# shield.net
KiCad netlist of a schematic drawn in EAGLE
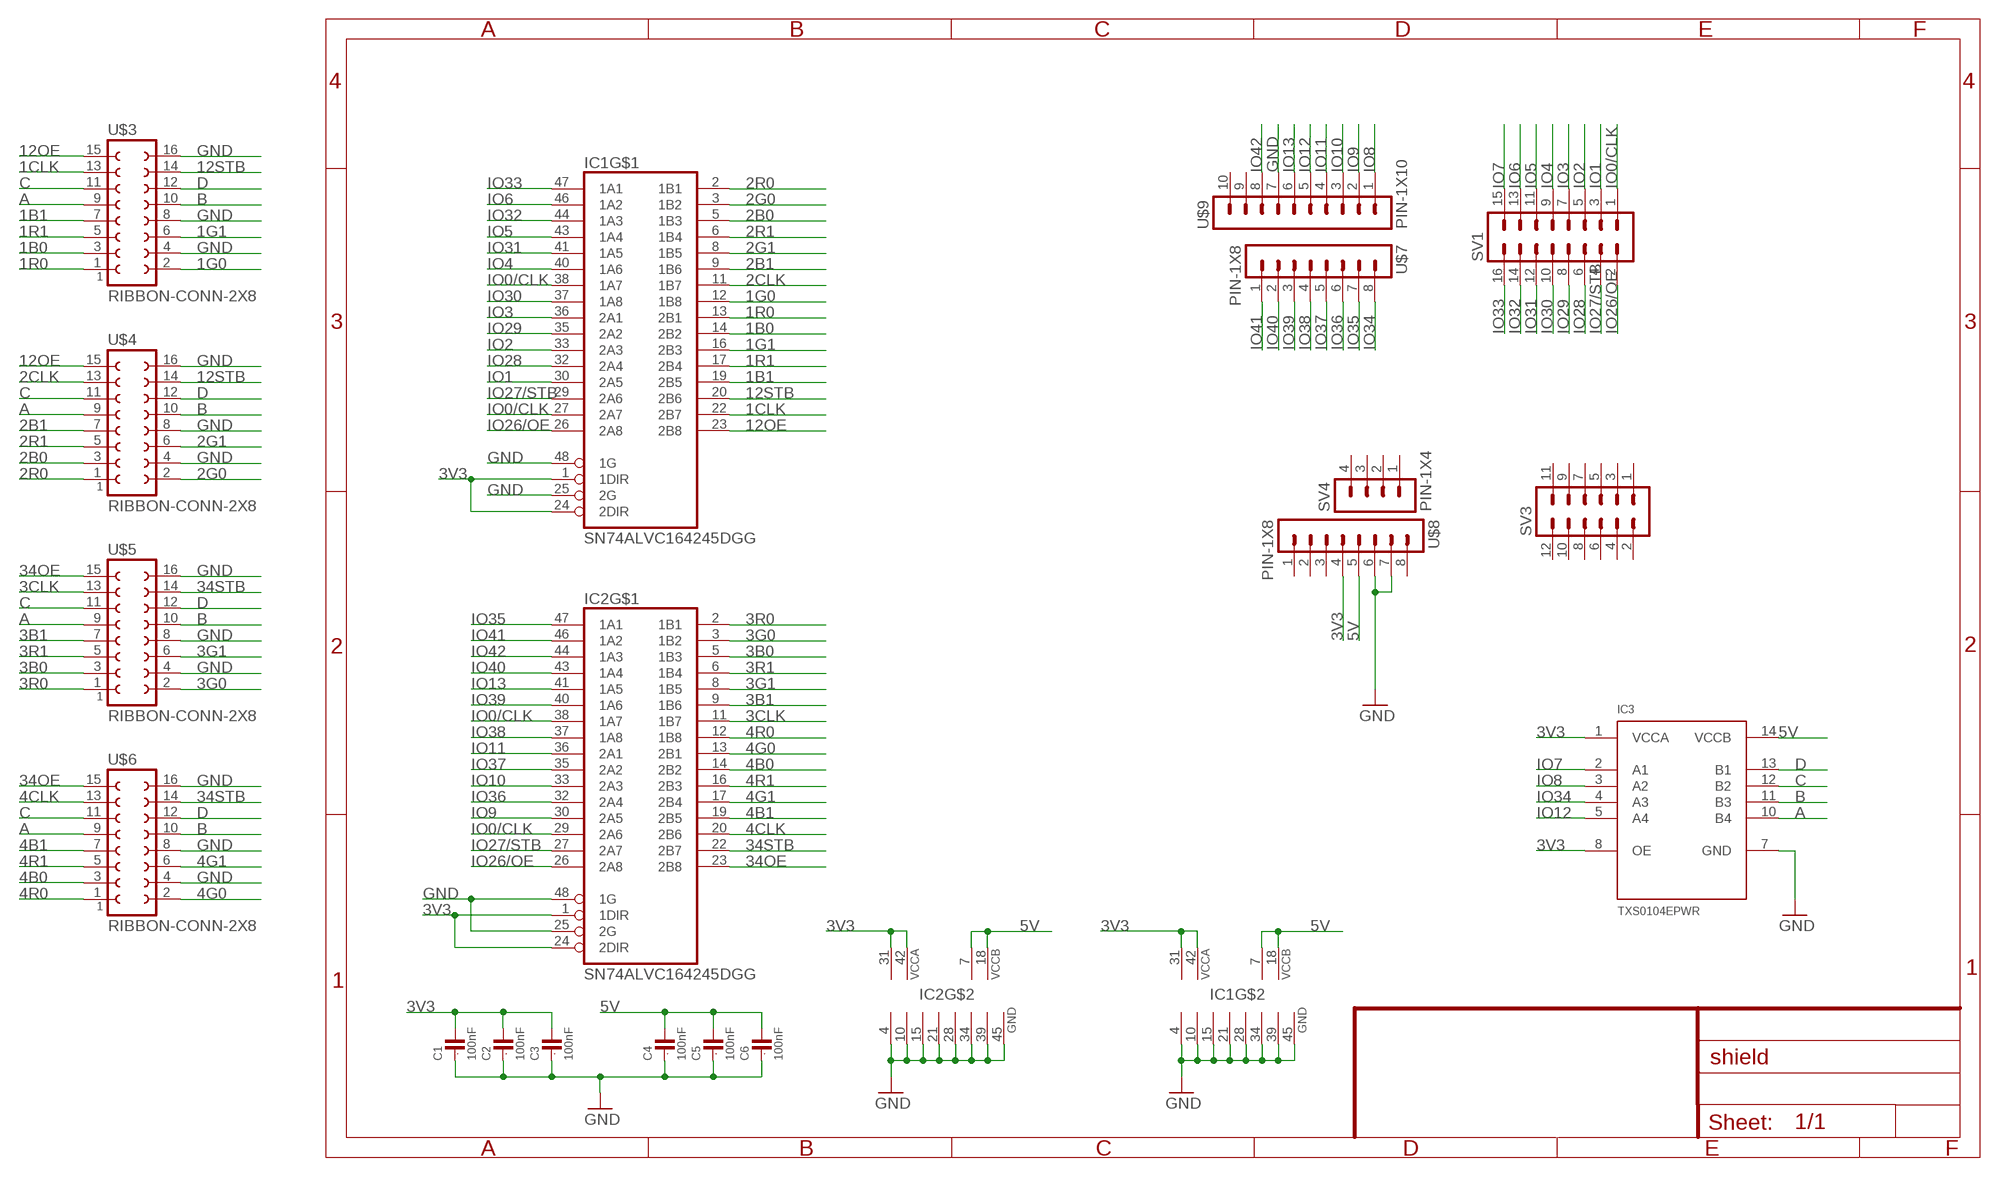
[diagram p0: schematic, sheet 1]

(export (version "E")
  (design (tool "Eeschema 10.0.6"))
  (components
    (comp (ref "C1")
      (value "100nF")
      (footprint "eagle-import:0603")
      (libsource (lib "eagle-import") (part "C0603"))
    )
    (comp (ref "C2")
      (value "100nF")
      (footprint "eagle-import:0603")
      (libsource (lib "eagle-import") (part "C0603"))
    )
    (comp (ref "C3")
      (value "100nF")
      (footprint "eagle-import:0603")
      (libsource (lib "eagle-import") (part "C0603"))
    )
    (comp (ref "C4")
      (value "100nF")
      (footprint "eagle-import:0603")
      (libsource (lib "eagle-import") (part "C0603"))
    )
    (comp (ref "C5")
      (value "100nF")
      (footprint "eagle-import:0603")
      (libsource (lib "eagle-import") (part "C0603"))
    )
    (comp (ref "C6")
      (value "100nF")
      (footprint "eagle-import:0603")
      (libsource (lib "eagle-import") (part "C0603"))
    )
    (comp (ref "IC1")
      (value "SN74ALVC164245DGG")
      (footprint "eagle-import:TSSOP48")
      (libsource (lib "eagle-import") (part "SN74ALVC164245DGG"))
    )
    (comp (ref "IC2")
      (value "SN74ALVC164245DGG")
      (footprint "eagle-import:TSSOP48")
      (libsource (lib "eagle-import") (part "SN74ALVC164245DGG"))
    )
    (comp (ref "IC3")
      (value "TXS0104EPWR")
      (footprint "eagle-import:TSSOP14")
      (libsource (lib "eagle-import") (part "TXS0104EPWR"))
    )
    (comp (ref "SV1")
      (value "MA08-2")
      (footprint "eagle-import:MA08-2")
      (libsource (lib "eagle-import") (part "MA08-2"))
    )
    (comp (ref "SV3")
      (value "MA06-2")
      (footprint "eagle-import:MA06-2")
      (libsource (lib "eagle-import") (part "MA06-2"))
    )
    (comp (ref "SV4")
      (value "PIN-1X4")
      (footprint "eagle-import:PIN-1X4")
      (libsource (lib "eagle-import") (part "PIN-1X4"))
    )
    (comp (ref "U$3")
      (value "RIBBON-CONN-2X8")
      (footprint "eagle-import:RIBBON-CONN-2X8")
      (libsource (lib "eagle-import") (part "RIBBON-CONN-2X8"))
    )
    (comp (ref "U$4")
      (value "RIBBON-CONN-2X8")
      (footprint "eagle-import:RIBBON-CONN-2X8")
      (libsource (lib "eagle-import") (part "RIBBON-CONN-2X8"))
    )
    (comp (ref "U$5")
      (value "RIBBON-CONN-2X8")
      (footprint "eagle-import:RIBBON-CONN-2X8")
      (libsource (lib "eagle-import") (part "RIBBON-CONN-2X8"))
    )
    (comp (ref "U$6")
      (value "RIBBON-CONN-2X8")
      (footprint "eagle-import:RIBBON-CONN-2X8")
      (libsource (lib "eagle-import") (part "RIBBON-CONN-2X8"))
    )
    (comp (ref "U$7")
      (value "PIN-1X8")
      (footprint "eagle-import:PIN-1X8")
      (libsource (lib "eagle-import") (part "PIN-1X8"))
    )
    (comp (ref "U$8")
      (value "PIN-1X8")
      (footprint "eagle-import:PIN-1X8")
      (libsource (lib "eagle-import") (part "PIN-1X8"))
    )
    (comp (ref "U$9")
      (value "PIN-1X10")
      (footprint "eagle-import:PIN-1X10")
      (libsource (lib "eagle-import") (part "PIN-1X10"))
    )
  )
  (nets
    (net (code "1") (name "/1B0") (class "Default")
      (node (ref "IC1") (pin "14") (pinfunction "2B2_14") (pintype "bidirectional"))
      (node (ref "U$3") (pin "3") (pinfunction "3_3") (pintype "passive"))
    )
    (net (code "2") (name "/1B1") (class "Default")
      (node (ref "IC1") (pin "19") (pinfunction "2B5_19") (pintype "bidirectional"))
      (node (ref "U$3") (pin "7") (pinfunction "7_7") (pintype "passive"))
    )
    (net (code "3") (name "/1CLK") (class "Default")
      (node (ref "IC1") (pin "22") (pinfunction "2B7_22") (pintype "bidirectional"))
      (node (ref "U$3") (pin "13") (pinfunction "13_13") (pintype "passive"))
    )
    (net (code "4") (name "/1G0") (class "Default")
      (node (ref "IC1") (pin "12") (pinfunction "1B8_12") (pintype "bidirectional"))
      (node (ref "U$3") (pin "2") (pinfunction "2_2") (pintype "passive"))
    )
    (net (code "5") (name "/1G1") (class "Default")
      (node (ref "IC1") (pin "16") (pinfunction "2B3_16") (pintype "bidirectional"))
      (node (ref "U$3") (pin "6") (pinfunction "6_6") (pintype "passive"))
    )
    (net (code "6") (name "/1R0") (class "Default")
      (node (ref "IC1") (pin "13") (pinfunction "2B1_13") (pintype "bidirectional"))
      (node (ref "U$3") (pin "1") (pinfunction "1_1") (pintype "passive"))
    )
    (net (code "7") (name "/1R1") (class "Default")
      (node (ref "IC1") (pin "17") (pinfunction "2B4_17") (pintype "bidirectional"))
      (node (ref "U$3") (pin "5") (pinfunction "5_5") (pintype "passive"))
    )
    (net (code "8") (name "/2B0") (class "Default")
      (node (ref "IC1") (pin "5") (pinfunction "1B3_5") (pintype "bidirectional"))
      (node (ref "U$4") (pin "3") (pinfunction "3_3") (pintype "passive"))
    )
    (net (code "9") (name "/2B1") (class "Default")
      (node (ref "IC1") (pin "9") (pinfunction "1B6_9") (pintype "bidirectional"))
      (node (ref "U$4") (pin "7") (pinfunction "7_7") (pintype "passive"))
    )
    (net (code "10") (name "/2CLK") (class "Default")
      (node (ref "IC1") (pin "11") (pinfunction "1B7_11") (pintype "bidirectional"))
      (node (ref "U$4") (pin "13") (pinfunction "13_13") (pintype "passive"))
    )
    (net (code "11") (name "/2G0") (class "Default")
      (node (ref "IC1") (pin "3") (pinfunction "1B2_3") (pintype "bidirectional"))
      (node (ref "U$4") (pin "2") (pinfunction "2_2") (pintype "passive"))
    )
    (net (code "12") (name "/2G1") (class "Default")
      (node (ref "IC1") (pin "8") (pinfunction "1B5_8") (pintype "bidirectional"))
      (node (ref "U$4") (pin "6") (pinfunction "6_6") (pintype "passive"))
    )
    (net (code "13") (name "/2R0") (class "Default")
      (node (ref "IC1") (pin "2") (pinfunction "1B1_2") (pintype "bidirectional"))
      (node (ref "U$4") (pin "1") (pinfunction "1_1") (pintype "passive"))
    )
    (net (code "14") (name "/2R1") (class "Default")
      (node (ref "IC1") (pin "6") (pinfunction "1B4_6") (pintype "bidirectional"))
      (node (ref "U$4") (pin "5") (pinfunction "5_5") (pintype "passive"))
    )
    (net (code "15") (name "/3B0") (class "Default")
      (node (ref "IC2") (pin "5") (pinfunction "1B3_5") (pintype "bidirectional"))
      (node (ref "U$5") (pin "3") (pinfunction "3_3") (pintype "passive"))
    )
    (net (code "16") (name "/3B1") (class "Default")
      (node (ref "IC2") (pin "9") (pinfunction "1B6_9") (pintype "bidirectional"))
      (node (ref "U$5") (pin "7") (pinfunction "7_7") (pintype "passive"))
    )
    (net (code "17") (name "/3CLK") (class "Default")
      (node (ref "IC2") (pin "11") (pinfunction "1B7_11") (pintype "bidirectional"))
      (node (ref "U$5") (pin "13") (pinfunction "13_13") (pintype "passive"))
    )
    (net (code "18") (name "/3G0") (class "Default")
      (node (ref "IC2") (pin "3") (pinfunction "1B2_3") (pintype "bidirectional"))
      (node (ref "U$5") (pin "2") (pinfunction "2_2") (pintype "passive"))
    )
    (net (code "19") (name "/3G1") (class "Default")
      (node (ref "IC2") (pin "8") (pinfunction "1B5_8") (pintype "bidirectional"))
      (node (ref "U$5") (pin "6") (pinfunction "6_6") (pintype "passive"))
    )
    (net (code "20") (name "/3R0") (class "Default")
      (node (ref "IC2") (pin "2") (pinfunction "1B1_2") (pintype "bidirectional"))
      (node (ref "U$5") (pin "1") (pinfunction "1_1") (pintype "passive"))
    )
    (net (code "21") (name "/3R1") (class "Default")
      (node (ref "IC2") (pin "6") (pinfunction "1B4_6") (pintype "bidirectional"))
      (node (ref "U$5") (pin "5") (pinfunction "5_5") (pintype "passive"))
    )
    (net (code "22") (name "/3V3") (class "Default")
      (node (ref "C1") (pin "2") (pinfunction "2_2") (pintype "passive"))
      (node (ref "C2") (pin "2") (pinfunction "2_2") (pintype "passive"))
      (node (ref "C3") (pin "2") (pinfunction "2_2") (pintype "passive"))
      (node (ref "IC1") (pin "1") (pinfunction "1DIR_1") (pintype "input"))
      (node (ref "IC1") (pin "24") (pinfunction "2DIR_24") (pintype "input"))
      (node (ref "IC1") (pin "31") (pinfunction "VCCA_31") (pintype "power_in"))
      (node (ref "IC1") (pin "42") (pinfunction "VCCA_42") (pintype "power_in"))
      (node (ref "IC2") (pin "1") (pinfunction "1DIR_1") (pintype "input"))
      (node (ref "IC2") (pin "24") (pinfunction "2DIR_24") (pintype "input"))
      (node (ref "IC2") (pin "31") (pinfunction "VCCA_31") (pintype "power_in"))
      (node (ref "IC2") (pin "42") (pinfunction "VCCA_42") (pintype "power_in"))
      (node (ref "IC3") (pin "1") (pinfunction "VCCA_1") (pintype "power_in"))
      (node (ref "IC3") (pin "8") (pinfunction "OE_8") (pintype "input"))
      (node (ref "U$8") (pin "4") (pinfunction "4_4") (pintype "passive"))
    )
    (net (code "23") (name "/4B0") (class "Default")
      (node (ref "IC2") (pin "14") (pinfunction "2B2_14") (pintype "bidirectional"))
      (node (ref "U$6") (pin "3") (pinfunction "3_3") (pintype "passive"))
    )
    (net (code "24") (name "/4B1") (class "Default")
      (node (ref "IC2") (pin "19") (pinfunction "2B5_19") (pintype "bidirectional"))
      (node (ref "U$6") (pin "7") (pinfunction "7_7") (pintype "passive"))
    )
    (net (code "25") (name "/4CLK") (class "Default")
      (node (ref "IC2") (pin "20") (pinfunction "2B6_20") (pintype "bidirectional"))
      (node (ref "U$6") (pin "13") (pinfunction "13_13") (pintype "passive"))
    )
    (net (code "26") (name "/4G0") (class "Default")
      (node (ref "IC2") (pin "13") (pinfunction "2B1_13") (pintype "bidirectional"))
      (node (ref "U$6") (pin "2") (pinfunction "2_2") (pintype "passive"))
    )
    (net (code "27") (name "/4G1") (class "Default")
      (node (ref "IC2") (pin "17") (pinfunction "2B4_17") (pintype "bidirectional"))
      (node (ref "U$6") (pin "6") (pinfunction "6_6") (pintype "passive"))
    )
    (net (code "28") (name "/4R0") (class "Default")
      (node (ref "IC2") (pin "12") (pinfunction "1B8_12") (pintype "bidirectional"))
      (node (ref "U$6") (pin "1") (pinfunction "1_1") (pintype "passive"))
    )
    (net (code "29") (name "/4R1") (class "Default")
      (node (ref "IC2") (pin "16") (pinfunction "2B3_16") (pintype "bidirectional"))
      (node (ref "U$6") (pin "5") (pinfunction "5_5") (pintype "passive"))
    )
    (net (code "30") (name "/5V") (class "Default")
      (node (ref "C4") (pin "2") (pinfunction "2_2") (pintype "passive"))
      (node (ref "C5") (pin "2") (pinfunction "2_2") (pintype "passive"))
      (node (ref "C6") (pin "2") (pinfunction "2_2") (pintype "passive"))
      (node (ref "IC1") (pin "18") (pinfunction "VCCB_18") (pintype "power_in"))
      (node (ref "IC1") (pin "7") (pinfunction "VCCB_7") (pintype "power_in"))
      (node (ref "IC2") (pin "18") (pinfunction "VCCB_18") (pintype "power_in"))
      (node (ref "IC2") (pin "7") (pinfunction "VCCB_7") (pintype "power_in"))
      (node (ref "IC3") (pin "14") (pinfunction "VCCB_14") (pintype "power_in"))
      (node (ref "U$8") (pin "5") (pinfunction "5_5") (pintype "passive"))
    )
    (net (code "31") (name "/12OE") (class "Default")
      (node (ref "IC1") (pin "23") (pinfunction "2B8_23") (pintype "bidirectional"))
      (node (ref "U$3") (pin "15") (pinfunction "15_15") (pintype "passive"))
      (node (ref "U$4") (pin "15") (pinfunction "15_15") (pintype "passive"))
    )
    (net (code "32") (name "/12STB") (class "Default")
      (node (ref "IC1") (pin "20") (pinfunction "2B6_20") (pintype "bidirectional"))
      (node (ref "U$3") (pin "14") (pinfunction "14_14") (pintype "passive"))
      (node (ref "U$4") (pin "14") (pinfunction "14_14") (pintype "passive"))
    )
    (net (code "33") (name "/34OE") (class "Default")
      (node (ref "IC2") (pin "23") (pinfunction "2B8_23") (pintype "bidirectional"))
      (node (ref "U$5") (pin "15") (pinfunction "15_15") (pintype "passive"))
      (node (ref "U$6") (pin "15") (pinfunction "15_15") (pintype "passive"))
    )
    (net (code "34") (name "/34STB") (class "Default")
      (node (ref "IC2") (pin "22") (pinfunction "2B7_22") (pintype "bidirectional"))
      (node (ref "U$5") (pin "14") (pinfunction "14_14") (pintype "passive"))
      (node (ref "U$6") (pin "14") (pinfunction "14_14") (pintype "passive"))
    )
    (net (code "35") (name "/A") (class "Default")
      (node (ref "IC3") (pin "10") (pinfunction "B4_10") (pintype "bidirectional"))
      (node (ref "U$3") (pin "9") (pinfunction "9_9") (pintype "passive"))
      (node (ref "U$4") (pin "9") (pinfunction "9_9") (pintype "passive"))
      (node (ref "U$5") (pin "9") (pinfunction "9_9") (pintype "passive"))
      (node (ref "U$6") (pin "9") (pinfunction "9_9") (pintype "passive"))
    )
    (net (code "36") (name "/B") (class "Default")
      (node (ref "IC3") (pin "11") (pinfunction "B3_11") (pintype "bidirectional"))
      (node (ref "U$3") (pin "10") (pinfunction "10_10") (pintype "passive"))
      (node (ref "U$4") (pin "10") (pinfunction "10_10") (pintype "passive"))
      (node (ref "U$5") (pin "10") (pinfunction "10_10") (pintype "passive"))
      (node (ref "U$6") (pin "10") (pinfunction "10_10") (pintype "passive"))
    )
    (net (code "37") (name "/C") (class "Default")
      (node (ref "IC3") (pin "12") (pinfunction "B2_12") (pintype "bidirectional"))
      (node (ref "U$3") (pin "11") (pinfunction "11_11") (pintype "passive"))
      (node (ref "U$4") (pin "11") (pinfunction "11_11") (pintype "passive"))
      (node (ref "U$5") (pin "11") (pinfunction "11_11") (pintype "passive"))
      (node (ref "U$6") (pin "11") (pinfunction "11_11") (pintype "passive"))
    )
    (net (code "38") (name "/D") (class "Default")
      (node (ref "IC3") (pin "13") (pinfunction "B1_13") (pintype "bidirectional"))
      (node (ref "U$3") (pin "12") (pinfunction "12_12") (pintype "passive"))
      (node (ref "U$4") (pin "12") (pinfunction "12_12") (pintype "passive"))
      (node (ref "U$5") (pin "12") (pinfunction "12_12") (pintype "passive"))
      (node (ref "U$6") (pin "12") (pinfunction "12_12") (pintype "passive"))
    )
    (net (code "39") (name "/IO0{slash}CLK") (class "Default")
      (node (ref "IC1") (pin "27") (pinfunction "2A7_27") (pintype "bidirectional"))
      (node (ref "IC1") (pin "38") (pinfunction "1A7_38") (pintype "bidirectional"))
      (node (ref "IC2") (pin "29") (pinfunction "2A6_29") (pintype "bidirectional"))
      (node (ref "IC2") (pin "38") (pinfunction "1A7_38") (pintype "bidirectional"))
      (node (ref "SV1") (pin "1") (pinfunction "1_1") (pintype "passive"))
    )
    (net (code "40") (name "/IO1") (class "Default")
      (node (ref "IC1") (pin "30") (pinfunction "2A5_30") (pintype "bidirectional"))
      (node (ref "SV1") (pin "3") (pinfunction "3_3") (pintype "passive"))
    )
    (net (code "41") (name "/IO2") (class "Default")
      (node (ref "IC1") (pin "33") (pinfunction "2A3_33") (pintype "bidirectional"))
      (node (ref "SV1") (pin "5") (pinfunction "5_5") (pintype "passive"))
    )
    (net (code "42") (name "/IO3") (class "Default")
      (node (ref "IC1") (pin "36") (pinfunction "2A1_36") (pintype "bidirectional"))
      (node (ref "SV1") (pin "7") (pinfunction "7_7") (pintype "passive"))
    )
    (net (code "43") (name "/IO4") (class "Default")
      (node (ref "IC1") (pin "40") (pinfunction "1A6_40") (pintype "bidirectional"))
      (node (ref "SV1") (pin "9") (pinfunction "9_9") (pintype "passive"))
    )
    (net (code "44") (name "/IO5") (class "Default")
      (node (ref "IC1") (pin "43") (pinfunction "1A4_43") (pintype "bidirectional"))
      (node (ref "SV1") (pin "11") (pinfunction "11_11") (pintype "passive"))
    )
    (net (code "45") (name "/IO6") (class "Default")
      (node (ref "IC1") (pin "46") (pinfunction "1A2_46") (pintype "bidirectional"))
      (node (ref "SV1") (pin "13") (pinfunction "13_13") (pintype "passive"))
    )
    (net (code "46") (name "/IO7") (class "Default")
      (node (ref "IC3") (pin "2") (pinfunction "A1_2") (pintype "bidirectional"))
      (node (ref "SV1") (pin "15") (pinfunction "15_15") (pintype "passive"))
    )
    (net (code "47") (name "/IO8") (class "Default")
      (node (ref "IC3") (pin "3") (pinfunction "A2_3") (pintype "bidirectional"))
      (node (ref "U$9") (pin "1") (pinfunction "1_1") (pintype "passive"))
    )
    (net (code "48") (name "/IO9") (class "Default")
      (node (ref "IC2") (pin "30") (pinfunction "2A5_30") (pintype "bidirectional"))
      (node (ref "U$9") (pin "2") (pinfunction "2_2") (pintype "passive"))
    )
    (net (code "49") (name "/IO10") (class "Default")
      (node (ref "IC2") (pin "33") (pinfunction "2A3_33") (pintype "bidirectional"))
      (node (ref "U$9") (pin "3") (pinfunction "3_3") (pintype "passive"))
    )
    (net (code "50") (name "/IO11") (class "Default")
      (node (ref "IC2") (pin "36") (pinfunction "2A1_36") (pintype "bidirectional"))
      (node (ref "U$9") (pin "4") (pinfunction "4_4") (pintype "passive"))
    )
    (net (code "51") (name "/IO12") (class "Default")
      (node (ref "IC3") (pin "5") (pinfunction "A4_5") (pintype "bidirectional"))
      (node (ref "U$9") (pin "5") (pinfunction "5_5") (pintype "passive"))
    )
    (net (code "52") (name "/IO13") (class "Default")
      (node (ref "IC2") (pin "41") (pinfunction "1A5_41") (pintype "bidirectional"))
      (node (ref "U$9") (pin "6") (pinfunction "6_6") (pintype "passive"))
    )
    (net (code "53") (name "/IO26{slash}OE") (class "Default")
      (node (ref "IC1") (pin "26") (pinfunction "2A8_26") (pintype "bidirectional"))
      (node (ref "IC2") (pin "26") (pinfunction "2A8_26") (pintype "bidirectional"))
      (node (ref "SV1") (pin "2") (pinfunction "2_2") (pintype "passive"))
    )
    (net (code "54") (name "/IO27{slash}STB") (class "Default")
      (node (ref "IC1") (pin "29") (pinfunction "2A6_29") (pintype "bidirectional"))
      (node (ref "IC2") (pin "27") (pinfunction "2A7_27") (pintype "bidirectional"))
      (node (ref "SV1") (pin "4") (pinfunction "4_4") (pintype "passive"))
    )
    (net (code "55") (name "/IO28") (class "Default")
      (node (ref "IC1") (pin "32") (pinfunction "2A4_32") (pintype "bidirectional"))
      (node (ref "SV1") (pin "6") (pinfunction "6_6") (pintype "passive"))
    )
    (net (code "56") (name "/IO29") (class "Default")
      (node (ref "IC1") (pin "35") (pinfunction "2A2_35") (pintype "bidirectional"))
      (node (ref "SV1") (pin "8") (pinfunction "8_8") (pintype "passive"))
    )
    (net (code "57") (name "/IO30") (class "Default")
      (node (ref "IC1") (pin "37") (pinfunction "1A8_37") (pintype "bidirectional"))
      (node (ref "SV1") (pin "10") (pinfunction "10_10") (pintype "passive"))
    )
    (net (code "58") (name "/IO31") (class "Default")
      (node (ref "IC1") (pin "41") (pinfunction "1A5_41") (pintype "bidirectional"))
      (node (ref "SV1") (pin "12") (pinfunction "12_12") (pintype "passive"))
    )
    (net (code "59") (name "/IO32") (class "Default")
      (node (ref "IC1") (pin "44") (pinfunction "1A3_44") (pintype "bidirectional"))
      (node (ref "SV1") (pin "14") (pinfunction "14_14") (pintype "passive"))
    )
    (net (code "60") (name "/IO33") (class "Default")
      (node (ref "IC1") (pin "47") (pinfunction "1A1_47") (pintype "bidirectional"))
      (node (ref "SV1") (pin "16") (pinfunction "16_16") (pintype "passive"))
    )
    (net (code "61") (name "/IO34") (class "Default")
      (node (ref "IC3") (pin "4") (pinfunction "A3_4") (pintype "bidirectional"))
      (node (ref "U$7") (pin "8") (pinfunction "8_8") (pintype "passive"))
    )
    (net (code "62") (name "/IO35") (class "Default")
      (node (ref "IC2") (pin "47") (pinfunction "1A1_47") (pintype "bidirectional"))
      (node (ref "U$7") (pin "7") (pinfunction "7_7") (pintype "passive"))
    )
    (net (code "63") (name "/IO36") (class "Default")
      (node (ref "IC2") (pin "32") (pinfunction "2A4_32") (pintype "bidirectional"))
      (node (ref "U$7") (pin "6") (pinfunction "6_6") (pintype "passive"))
    )
    (net (code "64") (name "/IO37") (class "Default")
      (node (ref "IC2") (pin "35") (pinfunction "2A2_35") (pintype "bidirectional"))
      (node (ref "U$7") (pin "5") (pinfunction "5_5") (pintype "passive"))
    )
    (net (code "65") (name "/IO38") (class "Default")
      (node (ref "IC2") (pin "37") (pinfunction "1A8_37") (pintype "bidirectional"))
      (node (ref "U$7") (pin "4") (pinfunction "4_4") (pintype "passive"))
    )
    (net (code "66") (name "/IO39") (class "Default")
      (node (ref "IC2") (pin "40") (pinfunction "1A6_40") (pintype "bidirectional"))
      (node (ref "U$7") (pin "3") (pinfunction "3_3") (pintype "passive"))
    )
    (net (code "67") (name "/IO40") (class "Default")
      (node (ref "IC2") (pin "43") (pinfunction "1A4_43") (pintype "bidirectional"))
      (node (ref "U$7") (pin "2") (pinfunction "2_2") (pintype "passive"))
    )
    (net (code "68") (name "/IO41") (class "Default")
      (node (ref "IC2") (pin "46") (pinfunction "1A2_46") (pintype "bidirectional"))
      (node (ref "U$7") (pin "1") (pinfunction "1_1") (pintype "passive"))
    )
    (net (code "69") (name "/IO42") (class "Default")
      (node (ref "IC2") (pin "44") (pinfunction "1A3_44") (pintype "bidirectional"))
      (node (ref "U$9") (pin "8") (pinfunction "8_8") (pintype "passive"))
    )
    (net (code "70") (name "GND") (class "Default")
      (node (ref "C1") (pin "1") (pinfunction "1_1") (pintype "passive"))
      (node (ref "C2") (pin "1") (pinfunction "1_1") (pintype "passive"))
      (node (ref "C3") (pin "1") (pinfunction "1_1") (pintype "passive"))
      (node (ref "C4") (pin "1") (pinfunction "1_1") (pintype "passive"))
      (node (ref "C5") (pin "1") (pinfunction "1_1") (pintype "passive"))
      (node (ref "C6") (pin "1") (pinfunction "1_1") (pintype "passive"))
      (node (ref "IC1") (pin "10") (pinfunction "GND_10") (pintype "power_in"))
      (node (ref "IC1") (pin "15") (pinfunction "GND_15") (pintype "power_in"))
      (node (ref "IC1") (pin "21") (pinfunction "GND_21") (pintype "power_in"))
      (node (ref "IC1") (pin "25") (pinfunction "2G_25") (pintype "input"))
      (node (ref "IC1") (pin "28") (pinfunction "GND_28") (pintype "power_in"))
      (node (ref "IC1") (pin "34") (pinfunction "GND_34") (pintype "power_in"))
      (node (ref "IC1") (pin "39") (pinfunction "GND_39") (pintype "power_in"))
      (node (ref "IC1") (pin "4") (pinfunction "GND_4") (pintype "power_in"))
      (node (ref "IC1") (pin "45") (pinfunction "GND_45") (pintype "power_in"))
      (node (ref "IC1") (pin "48") (pinfunction "1G_48") (pintype "input"))
      (node (ref "IC2") (pin "10") (pinfunction "GND_10") (pintype "power_in"))
      (node (ref "IC2") (pin "15") (pinfunction "GND_15") (pintype "power_in"))
      (node (ref "IC2") (pin "21") (pinfunction "GND_21") (pintype "power_in"))
      (node (ref "IC2") (pin "25") (pinfunction "2G_25") (pintype "input"))
      (node (ref "IC2") (pin "28") (pinfunction "GND_28") (pintype "power_in"))
      (node (ref "IC2") (pin "34") (pinfunction "GND_34") (pintype "power_in"))
      (node (ref "IC2") (pin "39") (pinfunction "GND_39") (pintype "power_in"))
      (node (ref "IC2") (pin "4") (pinfunction "GND_4") (pintype "power_in"))
      (node (ref "IC2") (pin "45") (pinfunction "GND_45") (pintype "power_in"))
      (node (ref "IC2") (pin "48") (pinfunction "1G_48") (pintype "input"))
      (node (ref "IC3") (pin "7") (pinfunction "GND_7") (pintype "power_in"))
      (node (ref "U$3") (pin "16") (pinfunction "16_16") (pintype "passive"))
      (node (ref "U$3") (pin "4") (pinfunction "4_4") (pintype "passive"))
      (node (ref "U$3") (pin "8") (pinfunction "8_8") (pintype "passive"))
      (node (ref "U$4") (pin "16") (pinfunction "16_16") (pintype "passive"))
      (node (ref "U$4") (pin "4") (pinfunction "4_4") (pintype "passive"))
      (node (ref "U$4") (pin "8") (pinfunction "8_8") (pintype "passive"))
      (node (ref "U$5") (pin "16") (pinfunction "16_16") (pintype "passive"))
      (node (ref "U$5") (pin "4") (pinfunction "4_4") (pintype "passive"))
      (node (ref "U$5") (pin "8") (pinfunction "8_8") (pintype "passive"))
      (node (ref "U$6") (pin "16") (pinfunction "16_16") (pintype "passive"))
      (node (ref "U$6") (pin "4") (pinfunction "4_4") (pintype "passive"))
      (node (ref "U$6") (pin "8") (pinfunction "8_8") (pintype "passive"))
      (node (ref "U$8") (pin "6") (pinfunction "6_6") (pintype "passive"))
      (node (ref "U$8") (pin "7") (pinfunction "7_7") (pintype "passive"))
      (node (ref "U$9") (pin "7") (pinfunction "7_7") (pintype "passive"))
    )
    (net (code "71") (name "unconnected-(SV3-Pad1)") (class "Default")
      (node (ref "SV3") (pin "1") (pinfunction "1_1") (pintype "passive"))
    )
    (net (code "72") (name "unconnected-(SV3-Pad2)") (class "Default")
      (node (ref "SV3") (pin "2") (pinfunction "2_2") (pintype "passive"))
    )
    (net (code "73") (name "unconnected-(SV3-Pad3)") (class "Default")
      (node (ref "SV3") (pin "3") (pinfunction "3_3") (pintype "passive"))
    )
    (net (code "74") (name "unconnected-(SV3-Pad4)") (class "Default")
      (node (ref "SV3") (pin "4") (pinfunction "4_4") (pintype "passive"))
    )
    (net (code "75") (name "unconnected-(SV3-Pad5)") (class "Default")
      (node (ref "SV3") (pin "5") (pinfunction "5_5") (pintype "passive"))
    )
    (net (code "76") (name "unconnected-(SV3-Pad6)") (class "Default")
      (node (ref "SV3") (pin "6") (pinfunction "6_6") (pintype "passive"))
    )
    (net (code "77") (name "unconnected-(SV3-Pad7)") (class "Default")
      (node (ref "SV3") (pin "7") (pinfunction "7_7") (pintype "passive"))
    )
    (net (code "78") (name "unconnected-(SV3-Pad8)") (class "Default")
      (node (ref "SV3") (pin "8") (pinfunction "8_8") (pintype "passive"))
    )
    (net (code "79") (name "unconnected-(SV3-Pad9)") (class "Default")
      (node (ref "SV3") (pin "9") (pinfunction "9_9") (pintype "passive"))
    )
    (net (code "80") (name "unconnected-(SV3-Pad10)") (class "Default")
      (node (ref "SV3") (pin "10") (pinfunction "10_10") (pintype "passive"))
    )
    (net (code "81") (name "unconnected-(SV3-Pad11)") (class "Default")
      (node (ref "SV3") (pin "11") (pinfunction "11_11") (pintype "passive"))
    )
    (net (code "82") (name "unconnected-(SV3-Pad12)") (class "Default")
      (node (ref "SV3") (pin "12") (pinfunction "12_12") (pintype "passive"))
    )
    (net (code "83") (name "unconnected-(SV4-Pad1)") (class "Default")
      (node (ref "SV4") (pin "1") (pinfunction "1_1") (pintype "passive"))
    )
    (net (code "84") (name "unconnected-(SV4-Pad2)") (class "Default")
      (node (ref "SV4") (pin "2") (pinfunction "2_2") (pintype "passive"))
    )
    (net (code "85") (name "unconnected-(SV4-Pad3)") (class "Default")
      (node (ref "SV4") (pin "3") (pinfunction "3_3") (pintype "passive"))
    )
    (net (code "86") (name "unconnected-(SV4-Pad4)") (class "Default")
      (node (ref "SV4") (pin "4") (pinfunction "4_4") (pintype "passive"))
    )
    (net (code "87") (name "unconnected-(U$8-Pad1)") (class "Default")
      (node (ref "U$8") (pin "1") (pinfunction "1_1") (pintype "passive"))
    )
    (net (code "88") (name "unconnected-(U$8-Pad2)") (class "Default")
      (node (ref "U$8") (pin "2") (pinfunction "2_2") (pintype "passive"))
    )
    (net (code "89") (name "unconnected-(U$8-Pad3)") (class "Default")
      (node (ref "U$8") (pin "3") (pinfunction "3_3") (pintype "passive"))
    )
    (net (code "90") (name "unconnected-(U$8-Pad8)") (class "Default")
      (node (ref "U$8") (pin "8") (pinfunction "8_8") (pintype "passive"))
    )
    (net (code "91") (name "unconnected-(U$9-Pad9)") (class "Default")
      (node (ref "U$9") (pin "9") (pinfunction "9_9") (pintype "passive"))
    )
    (net (code "92") (name "unconnected-(U$9-Pad10)") (class "Default")
      (node (ref "U$9") (pin "10") (pinfunction "10_10") (pintype "passive"))
    )
  )
)
